# connectors.net
KiCad netlist of a schematic drawn in Altium Designer
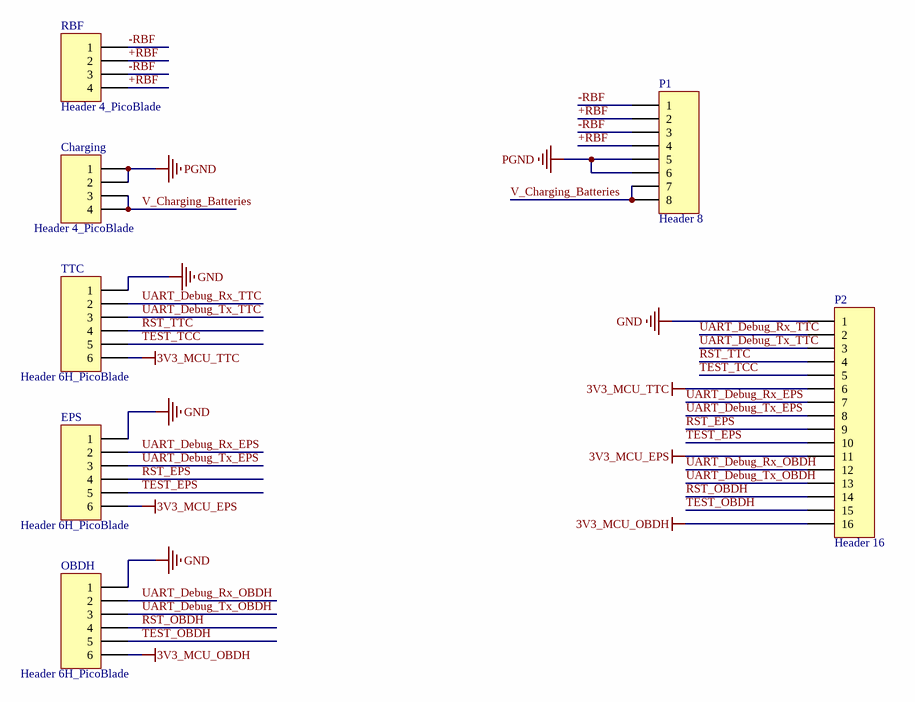
[diagram p0: connectors.SchDoc]

(export (version "E")
  (design (tool "Eeschema 10.0.6"))
  (components
    (comp (ref "Charging")
      (value "Header 4_PicoBlade")
      (footprint "HDR4 PicoBlade")
      (description "Header, 4-Pin")
      (fields (field (name "PARTNUMBER") "53398-0471") (field (name "PUBLISHER") "Altium Limited"))
      (libsource (lib "FloripaSatSchlib") (part "Header 4_PicoBlade"))
    )
    (comp (ref "EPS")
      (value "Header 6H_PicoBlade")
      (footprint "HDR6 PicoBlade")
      (description "Header, 6-Pin, Right Angle")
      (fields (field (name "PARTNUMBER") "53398-0671") (field (name "PUBLISHER") "Altium Limited"))
      (libsource (lib "FloripaSatSchlib") (part "Header 6H_PicoBlade"))
    )
    (comp (ref "OBDH")
      (value "Header 6H_PicoBlade")
      (footprint "HDR6 PicoBlade")
      (description "Header, 6-Pin, Right Angle")
      (fields (field (name "PARTNUMBER") "53398-0671") (field (name "PUBLISHER") "Altium Limited"))
      (libsource (lib "FloripaSatSchlib") (part "Header 6H_PicoBlade"))
    )
    (comp (ref "P1")
      (value "Header 8")
      (footprint "HDR1X8")
      (description "Header, 8-Pin")
      (fields (field (name "PUBLISHER") "Altium Limited"))
      (libsource (lib "Miscellaneous Connectors") (part "Header 8"))
    )
    (comp (ref "P2")
      (value "Header 16")
      (footprint "HDR1X16")
      (description "Header, 16-Pin")
      (fields (field (name "PUBLISHER") "Altium Limited"))
      (libsource (lib "Miscellaneous Connectors") (part "Header 16"))
    )
    (comp (ref "RBF")
      (value "Header 4_PicoBlade")
      (footprint "HDR4 PicoBlade")
      (description "Header, 4-Pin")
      (fields (field (name "PARTNUMBER") "53398-0471") (field (name "PUBLISHER") "Altium Limited"))
      (libsource (lib "FloripaSatSchlib") (part "Header 4_PicoBlade"))
    )
    (comp (ref "TTC")
      (value "Header 6H_PicoBlade")
      (footprint "HDR6 PicoBlade")
      (description "Header, 6-Pin, Right Angle")
      (fields (field (name "PARTNUMBER") "53398-0671") (field (name "PUBLISHER") "Altium Limited"))
      (libsource (lib "FloripaSatSchlib") (part "Header 6H_PicoBlade"))
    )
  )
  (nets
    (net (code "1") (name "/+RBF") (class "Default")
      (node (ref "P1") (pin "2") (pinfunction "2_2") (pintype "passive"))
      (node (ref "P1") (pin "4") (pinfunction "4_4") (pintype "passive"))
      (node (ref "RBF") (pin "2") (pinfunction "2_2") (pintype "passive"))
      (node (ref "RBF") (pin "4") (pinfunction "4_4") (pintype "passive"))
    )
    (net (code "2") (name "/-RBF") (class "Default")
      (node (ref "P1") (pin "1") (pinfunction "1_1") (pintype "passive"))
      (node (ref "P1") (pin "3") (pinfunction "3_3") (pintype "passive"))
      (node (ref "RBF") (pin "1") (pinfunction "1_1") (pintype "passive"))
      (node (ref "RBF") (pin "3") (pinfunction "3_3") (pintype "passive"))
    )
    (net (code "3") (name "/RST_EPS") (class "Default")
      (node (ref "EPS") (pin "4") (pinfunction "4_4") (pintype "passive"))
      (node (ref "P2") (pin "9") (pinfunction "9_9") (pintype "passive"))
    )
    (net (code "4") (name "/RST_OBDH") (class "Default")
      (node (ref "OBDH") (pin "4") (pinfunction "4_4") (pintype "passive"))
      (node (ref "P2") (pin "14") (pinfunction "14_14") (pintype "passive"))
    )
    (net (code "5") (name "/RST_TTC") (class "Default")
      (node (ref "P2") (pin "4") (pinfunction "4_4") (pintype "passive"))
      (node (ref "TTC") (pin "4") (pinfunction "4_4") (pintype "passive"))
    )
    (net (code "6") (name "/TEST_EPS") (class "Default")
      (node (ref "EPS") (pin "5") (pinfunction "5_5") (pintype "passive"))
      (node (ref "P2") (pin "10") (pinfunction "10_10") (pintype "passive"))
    )
    (net (code "7") (name "/TEST_OBDH") (class "Default")
      (node (ref "OBDH") (pin "5") (pinfunction "5_5") (pintype "passive"))
      (node (ref "P2") (pin "15") (pinfunction "15_15") (pintype "passive"))
    )
    (net (code "8") (name "/TEST_TCC") (class "Default")
      (node (ref "P2") (pin "5") (pinfunction "5_5") (pintype "passive"))
      (node (ref "TTC") (pin "5") (pinfunction "5_5") (pintype "passive"))
    )
    (net (code "9") (name "/UART_Debug_Rx_EPS") (class "Default")
      (node (ref "EPS") (pin "2") (pinfunction "2_2") (pintype "passive"))
      (node (ref "P2") (pin "7") (pinfunction "7_7") (pintype "passive"))
    )
    (net (code "10") (name "/UART_Debug_Rx_OBDH") (class "Default")
      (node (ref "OBDH") (pin "2") (pinfunction "2_2") (pintype "passive"))
      (node (ref "P2") (pin "12") (pinfunction "12_12") (pintype "passive"))
    )
    (net (code "11") (name "/UART_Debug_Rx_TTC") (class "Default")
      (node (ref "P2") (pin "2") (pinfunction "2_2") (pintype "passive"))
      (node (ref "TTC") (pin "2") (pinfunction "2_2") (pintype "passive"))
    )
    (net (code "12") (name "/UART_Debug_Tx_EPS") (class "Default")
      (node (ref "EPS") (pin "3") (pinfunction "3_3") (pintype "passive"))
      (node (ref "P2") (pin "8") (pinfunction "8_8") (pintype "passive"))
    )
    (net (code "13") (name "/UART_Debug_Tx_OBDH") (class "Default")
      (node (ref "OBDH") (pin "3") (pinfunction "3_3") (pintype "passive"))
      (node (ref "P2") (pin "13") (pinfunction "13_13") (pintype "passive"))
    )
    (net (code "14") (name "/UART_Debug_Tx_TTC") (class "Default")
      (node (ref "P2") (pin "3") (pinfunction "3_3") (pintype "passive"))
      (node (ref "TTC") (pin "3") (pinfunction "3_3") (pintype "passive"))
    )
    (net (code "15") (name "/V_Charging_Batteries") (class "Default")
      (node (ref "Charging") (pin "3") (pinfunction "3_3") (pintype "passive"))
      (node (ref "Charging") (pin "4") (pinfunction "4_4") (pintype "passive"))
      (node (ref "P1") (pin "7") (pinfunction "7_7") (pintype "passive"))
      (node (ref "P1") (pin "8") (pinfunction "8_8") (pintype "passive"))
    )
    (net (code "16") (name "3V3_MCU_EPS") (class "Default")
      (node (ref "EPS") (pin "6") (pinfunction "6_6") (pintype "passive"))
      (node (ref "P2") (pin "11") (pinfunction "11_11") (pintype "passive"))
    )
    (net (code "17") (name "3V3_MCU_OBDH") (class "Default")
      (node (ref "OBDH") (pin "6") (pinfunction "6_6") (pintype "passive"))
      (node (ref "P2") (pin "16") (pinfunction "16_16") (pintype "passive"))
    )
    (net (code "18") (name "3V3_MCU_TTC") (class "Default")
      (node (ref "P2") (pin "6") (pinfunction "6_6") (pintype "passive"))
      (node (ref "TTC") (pin "6") (pinfunction "6_6") (pintype "passive"))
    )
    (net (code "19") (name "GND") (class "Default")
      (node (ref "EPS") (pin "1") (pinfunction "1_1") (pintype "passive"))
      (node (ref "OBDH") (pin "1") (pinfunction "1_1") (pintype "passive"))
      (node (ref "P2") (pin "1") (pinfunction "1_1") (pintype "passive"))
      (node (ref "TTC") (pin "1") (pinfunction "1_1") (pintype "passive"))
    )
    (net (code "20") (name "PGND") (class "Default")
      (node (ref "Charging") (pin "1") (pinfunction "1_1") (pintype "passive"))
      (node (ref "Charging") (pin "2") (pinfunction "2_2") (pintype "passive"))
      (node (ref "P1") (pin "5") (pinfunction "5_5") (pintype "passive"))
      (node (ref "P1") (pin "6") (pinfunction "6_6") (pintype "passive"))
    )
  )
)
